# iMX6q_DDR3.net
KiCad netlist of a schematic drawn in Altium Designer
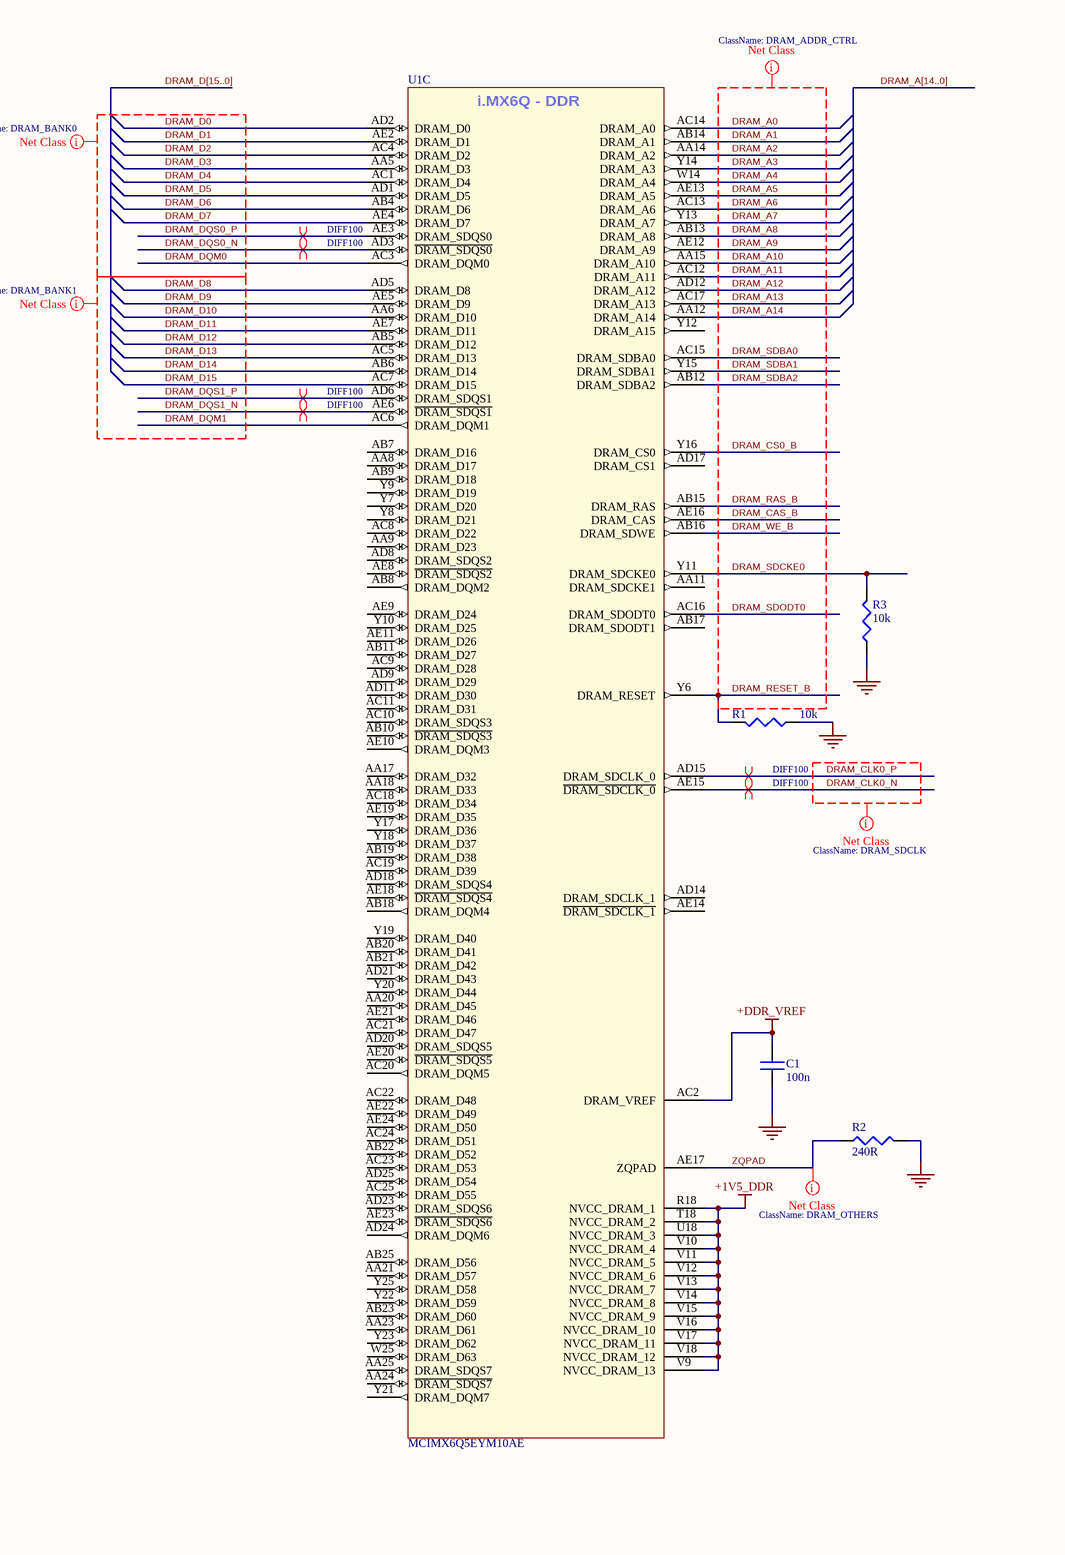
[diagram p0: iMX6q_DDR3.SchDoc, left]
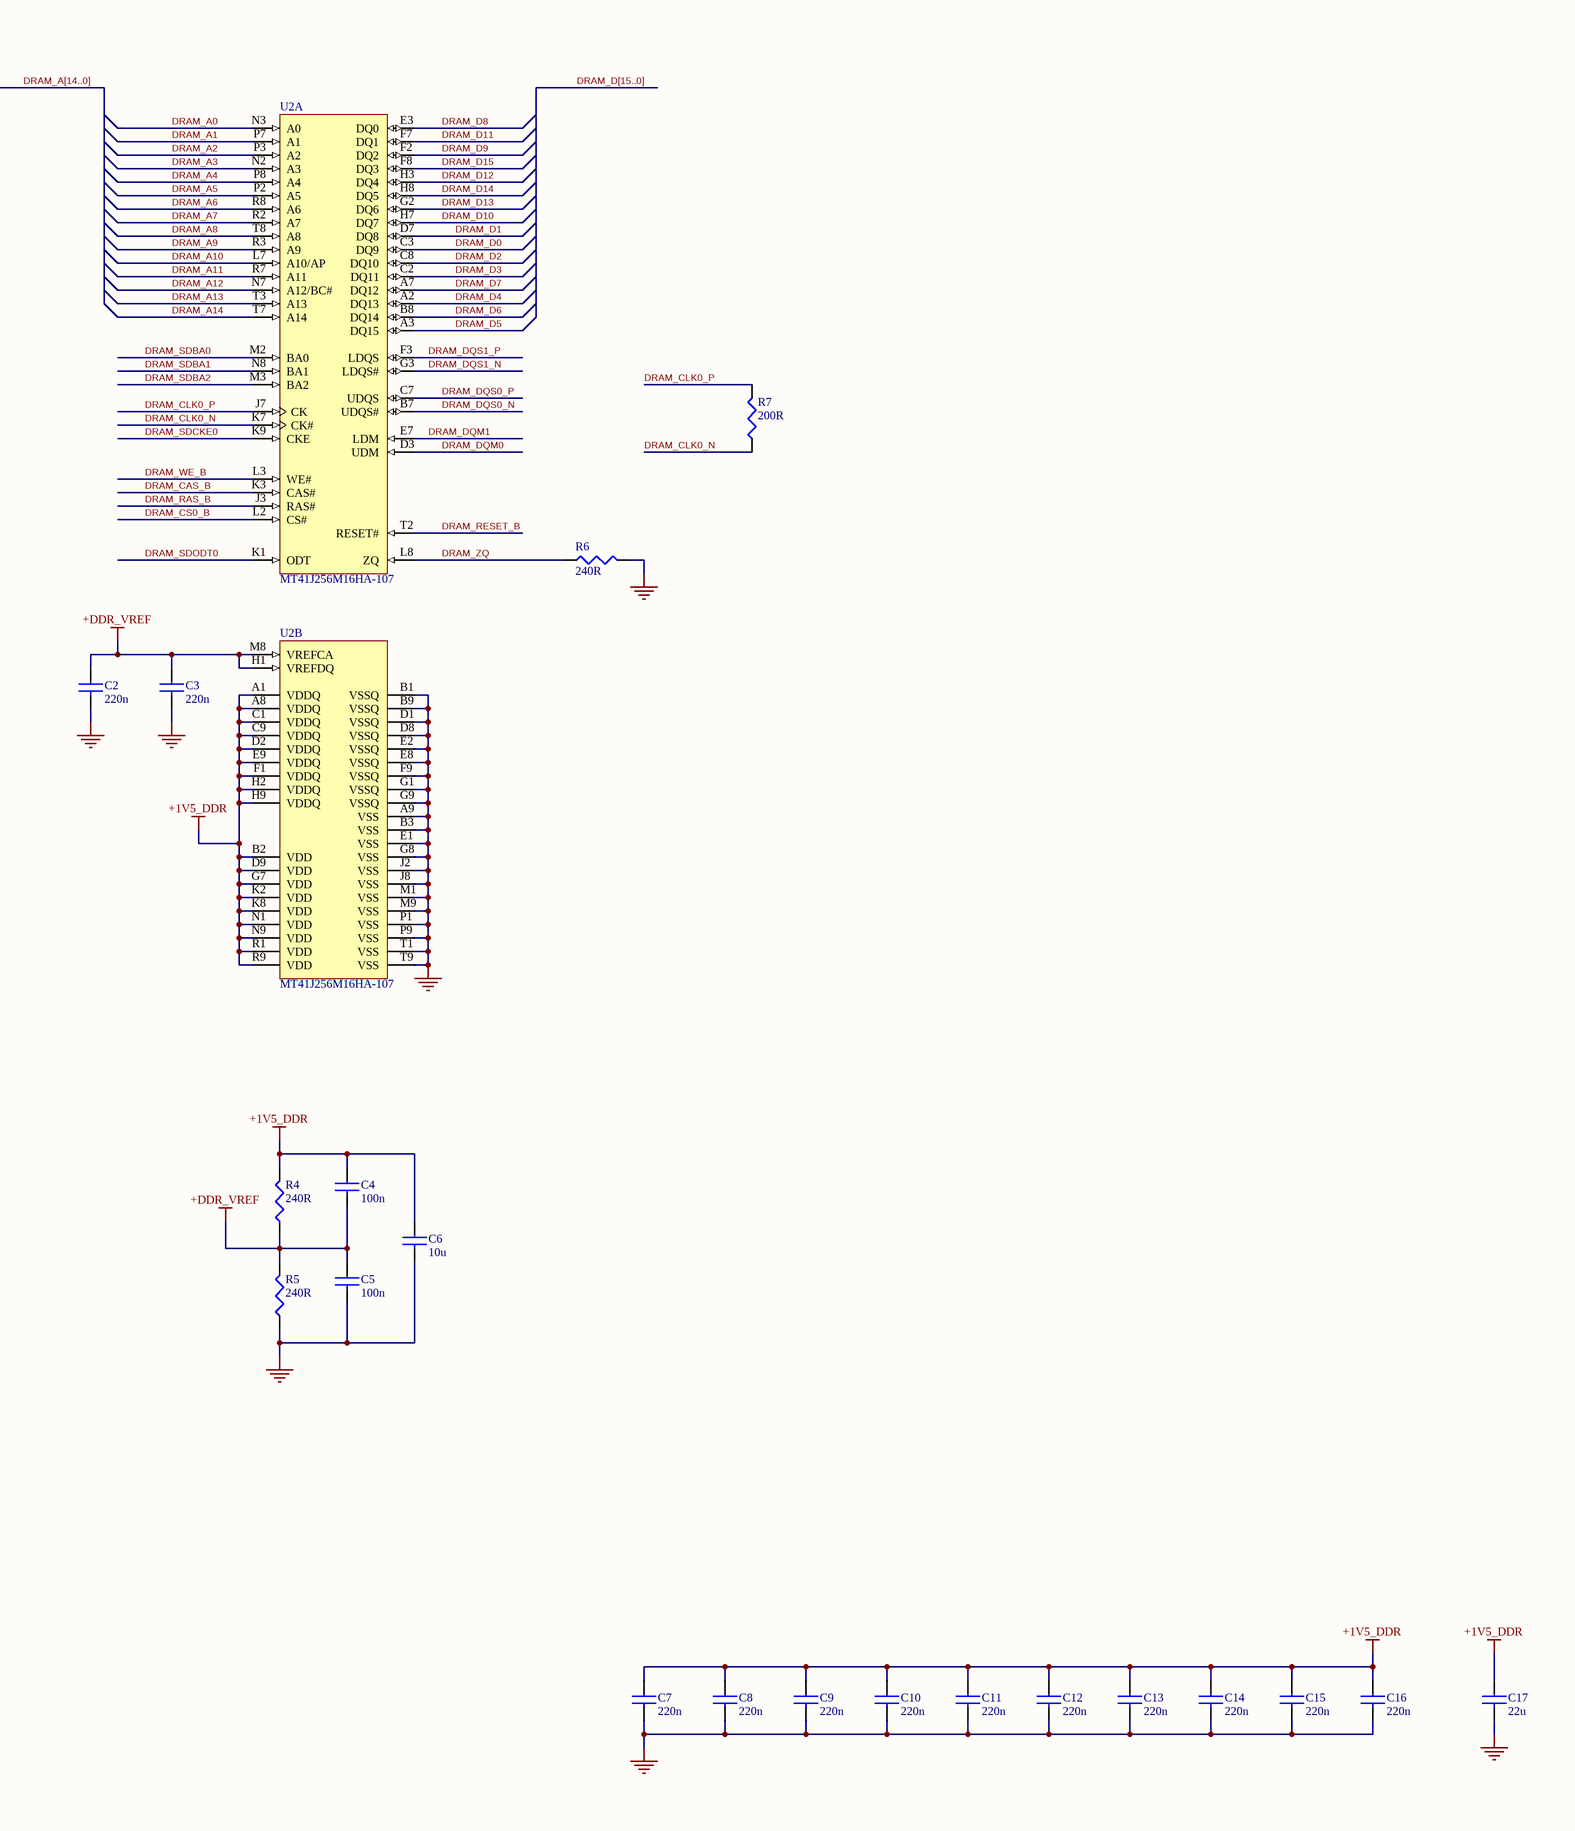
[diagram p1: iMX6q_DDR3.SchDoc, right]

(export (version "E")
  (design (tool "Eeschema 10.0.6"))
  (components
    (comp (ref "C1")
      (value "100n")
      (footprint "C0402")
      (description "CAP CER .10UF 50V X5R 10% 0402")
      (fields
        (field (name "MANUFACTURER") "TDK Corporation")
        (field (name "MANUFACTURER PART NUMBER") "C1005X5R1H104K")
      )
      (libsource (lib "iMX6 Rex_V1I1") (part "C1005X5R1H104K"))
    )
    (comp (ref "C2")
      (value "220n")
      (footprint "C0402")
      (description "CAP CER .22UF 25V X5R 20% 0402")
      (fields
        (field (name "MANUFACTURER") "TDK Corporation")
        (field (name "MANUFACTURER PART NUMBER") "C1005X5R1E224M")
      )
      (libsource (lib "iMX6 Rex_V1I1") (part "C1005X5R1E224M"))
    )
    (comp (ref "C3")
      (value "220n")
      (footprint "C0402")
      (description "CAP CER .22UF 25V X5R 20% 0402")
      (fields
        (field (name "MANUFACTURER") "TDK Corporation")
        (field (name "MANUFACTURER PART NUMBER") "C1005X5R1E224M")
      )
      (libsource (lib "iMX6 Rex_V1I1") (part "C1005X5R1E224M"))
    )
    (comp (ref "C4")
      (value "100n")
      (footprint "C0402")
      (description "CAP CER .10UF 50V X5R 10% 0402")
      (fields
        (field (name "MANUFACTURER") "TDK Corporation")
        (field (name "MANUFACTURER PART NUMBER") "C1005X5R1H104K")
      )
      (libsource (lib "iMX6 Rex_V1I1") (part "C1005X5R1H104K"))
    )
    (comp (ref "C5")
      (value "100n")
      (footprint "C0402")
      (description "CAP CER .10UF 50V X5R 10% 0402")
      (fields
        (field (name "MANUFACTURER") "TDK Corporation")
        (field (name "MANUFACTURER PART NUMBER") "C1005X5R1H104K")
      )
      (libsource (lib "iMX6 Rex_V1I1") (part "C1005X5R1H104K"))
    )
    (comp (ref "C6")
      (value "10u")
      (footprint "C0603")
      (description "CAP CER 10UF 6.3V X5R 20% 0603")
      (fields
        (field (name "MANUFACTURER") "TDK Corporation")
        (field (name "MANUFACTURER PART NUMBER") "C1608X5R0J106M")
      )
      (libsource (lib "iMX6 Rex_V1I1") (part "C1608X5R0J106M"))
    )
    (comp (ref "C7")
      (value "220n")
      (footprint "C0402")
      (description "CAP CER .22UF 25V X5R 20% 0402")
      (fields
        (field (name "MANUFACTURER") "TDK Corporation")
        (field (name "MANUFACTURER PART NUMBER") "C1005X5R1E224M")
      )
      (libsource (lib "iMX6 Rex_V1I1") (part "C1005X5R1E224M"))
    )
    (comp (ref "C8")
      (value "220n")
      (footprint "C0402")
      (description "CAP CER .22UF 25V X5R 20% 0402")
      (fields
        (field (name "MANUFACTURER") "TDK Corporation")
        (field (name "MANUFACTURER PART NUMBER") "C1005X5R1E224M")
      )
      (libsource (lib "iMX6 Rex_V1I1") (part "C1005X5R1E224M"))
    )
    (comp (ref "C9")
      (value "220n")
      (footprint "C0402")
      (description "CAP CER .22UF 25V X5R 20% 0402")
      (fields
        (field (name "MANUFACTURER") "TDK Corporation")
        (field (name "MANUFACTURER PART NUMBER") "C1005X5R1E224M")
      )
      (libsource (lib "iMX6 Rex_V1I1") (part "C1005X5R1E224M"))
    )
    (comp (ref "C10")
      (value "220n")
      (footprint "C0402")
      (description "CAP CER .22UF 25V X5R 20% 0402")
      (fields
        (field (name "MANUFACTURER") "TDK Corporation")
        (field (name "MANUFACTURER PART NUMBER") "C1005X5R1E224M")
      )
      (libsource (lib "iMX6 Rex_V1I1") (part "C1005X5R1E224M"))
    )
    (comp (ref "C11")
      (value "220n")
      (footprint "C0402")
      (description "CAP CER .22UF 25V X5R 20% 0402")
      (fields
        (field (name "MANUFACTURER") "TDK Corporation")
        (field (name "MANUFACTURER PART NUMBER") "C1005X5R1E224M")
      )
      (libsource (lib "iMX6 Rex_V1I1") (part "C1005X5R1E224M"))
    )
    (comp (ref "C12")
      (value "220n")
      (footprint "C0402")
      (description "CAP CER .22UF 25V X5R 20% 0402")
      (fields
        (field (name "MANUFACTURER") "TDK Corporation")
        (field (name "MANUFACTURER PART NUMBER") "C1005X5R1E224M")
      )
      (libsource (lib "iMX6 Rex_V1I1") (part "C1005X5R1E224M"))
    )
    (comp (ref "C13")
      (value "220n")
      (footprint "C0402")
      (description "CAP CER .22UF 25V X5R 20% 0402")
      (fields
        (field (name "MANUFACTURER") "TDK Corporation")
        (field (name "MANUFACTURER PART NUMBER") "C1005X5R1E224M")
      )
      (libsource (lib "iMX6 Rex_V1I1") (part "C1005X5R1E224M"))
    )
    (comp (ref "C14")
      (value "220n")
      (footprint "C0402")
      (description "CAP CER .22UF 25V X5R 20% 0402")
      (fields
        (field (name "MANUFACTURER") "TDK Corporation")
        (field (name "MANUFACTURER PART NUMBER") "C1005X5R1E224M")
      )
      (libsource (lib "iMX6 Rex_V1I1") (part "C1005X5R1E224M"))
    )
    (comp (ref "C15")
      (value "220n")
      (footprint "C0402")
      (description "CAP CER .22UF 25V X5R 20% 0402")
      (fields
        (field (name "MANUFACTURER") "TDK Corporation")
        (field (name "MANUFACTURER PART NUMBER") "C1005X5R1E224M")
      )
      (libsource (lib "iMX6 Rex_V1I1") (part "C1005X5R1E224M"))
    )
    (comp (ref "C16")
      (value "220n")
      (footprint "C0402")
      (description "CAP CER .22UF 25V X5R 20% 0402")
      (fields
        (field (name "MANUFACTURER") "TDK Corporation")
        (field (name "MANUFACTURER PART NUMBER") "C1005X5R1E224M")
      )
      (libsource (lib "iMX6 Rex_V1I1") (part "C1005X5R1E224M"))
    )
    (comp (ref "C17")
      (value "22u")
      (footprint "C0603")
      (description "CAP CER 22UF 4V 20% X5R 0603")
      (fields
        (field (name "MANUFACTURER") "Murata Electronics North America")
        (field (name "MANUFACTURER PART NUMBER") "GRM188R60G226MEA0L")
        (field (name ".CHECKED PCB") "RF, used by MM")
        (field (name ".CHECKED SCH") "MM, checked by RF")
        (field (name ".CREATOR") "MM")
      )
      (libsource (lib "iMX6 Rex_V1I1") (part "GRM188R60G226MEA0L"))
    )
    (comp (ref "R1")
      (value "10k")
      (footprint "R0402")
      (description "RES 10.0K OHM 1/16W 1% 0402 SMD")
      (fields
        (field (name "MANUFACTURER") "Yageo")
        (field (name "MANUFACTURER PART NUMBER") "RC0402FR-0710KL")
      )
      (libsource (lib "iMX6 Rex_V1I1") (part "RC0402FR-0710KL"))
    )
    (comp (ref "R2")
      (value "240R")
      (footprint "R0402")
      (description "RES TF 240 OHM 1% 0.0625W 0402")
      (fields
        (field (name "MANUFACTURER") "Stackpole Electronics Inc")
        (field (name "MANUFACTURER PART NUMBER") "RMCF0402FT240R")
      )
      (libsource (lib "iMX6 Rex_V1I1") (part "RMCF0402FT240R"))
    )
    (comp (ref "R3")
      (value "10k")
      (footprint "R0402")
      (description "RES 10.0K OHM 1/16W 1% 0402 SMD")
      (fields
        (field (name "MANUFACTURER") "Yageo")
        (field (name "MANUFACTURER PART NUMBER") "RC0402FR-0710KL")
      )
      (libsource (lib "iMX6 Rex_V1I1") (part "RC0402FR-0710KL"))
    )
    (comp (ref "R4")
      (value "240R")
      (footprint "R0402")
      (description "RES TF 240 OHM 1% 0.0625W 0402")
      (fields
        (field (name "MANUFACTURER") "Stackpole Electronics Inc")
        (field (name "MANUFACTURER PART NUMBER") "RMCF0402FT240R")
      )
      (libsource (lib "iMX6 Rex_V1I1") (part "RMCF0402FT240R"))
    )
    (comp (ref "R5")
      (value "240R")
      (footprint "R0402")
      (description "RES TF 240 OHM 1% 0.0625W 0402")
      (fields
        (field (name "MANUFACTURER") "Stackpole Electronics Inc")
        (field (name "MANUFACTURER PART NUMBER") "RMCF0402FT240R")
      )
      (libsource (lib "iMX6 Rex_V1I1") (part "RMCF0402FT240R"))
    )
    (comp (ref "R6")
      (value "240R")
      (footprint "R0402")
      (description "RES TF 240 OHM 1% 0.0625W 0402")
      (fields
        (field (name "MANUFACTURER") "Stackpole Electronics Inc")
        (field (name "MANUFACTURER PART NUMBER") "RMCF0402FT240R")
      )
      (libsource (lib "iMX6 Rex_V1I1") (part "RMCF0402FT240R"))
    )
    (comp (ref "R7")
      (value "200R")
      (footprint "R0402")
      (description "RES 200 OHM 1/16W 1% 0402 SMD")
      (fields
        (field (name "MANUFACTURER") "Vishay Dale")
        (field (name "MANUFACTURER PART NUMBER") "CRCW0402200RFKED")
        (field (name ".CHECKED PCB") "RF, used by MM")
        (field (name ".CHECKED SCH") "MM, checked by RF")
        (field (name ".CREATOR") "MM")
      )
      (libsource (lib "iMX6 Rex_V1I1") (part "CRCW0402200RFKED"))
    )
    (comp (ref "U1")
      (value "MCIMX6Q5EYM10AE")
      (footprint "PBGA624")
      (description "IC MCU 32BIT ARM QUAD 624FCBGA")
      (fields
        (field (name "MANUFACTURER") "Freescale Semiconductor")
        (field (name ".CREATOR") "MM")
        (field (name ".CHECKED PCB") "MM, checked by RF")
        (field (name ".CHECKED SCH") "MM")
      )
      (libsource (lib "iMX6 Rex_V1I1") (part "MCIMX6Q5EYM10AC"))
    )
    (comp (ref "U2")
      (value "MT41J256M16HA-107")
      (footprint "MICT-HA-96")
      (description "4Gb DDR3-1866 SDRAM, 256Mb x 16, 1.071ns, 1.5V, 0 to 95 degC, 96-Ball FBGA, Pb-Free")
      (fields (field (name "VOLTAGE") "1.5V ") (field (name "MANUFACTURER") "Micron"))
      (libsource (lib "Micron Memory DDR3 SDRAM") (part "MT41J256M16HA-107"))
    )
  )
  (nets
    (net (code "1") (name "+1V5_DDR") (class "Default")
      (node (ref "C10") (pin "1") (pinfunction "1_1") (pintype "passive"))
      (node (ref "C11") (pin "1") (pinfunction "1_1") (pintype "passive"))
      (node (ref "C12") (pin "1") (pinfunction "1_1") (pintype "passive"))
      (node (ref "C13") (pin "1") (pinfunction "1_1") (pintype "passive"))
      (node (ref "C14") (pin "1") (pinfunction "1_1") (pintype "passive"))
      (node (ref "C15") (pin "1") (pinfunction "1_1") (pintype "passive"))
      (node (ref "C16") (pin "1") (pinfunction "1_1") (pintype "passive"))
      (node (ref "C17") (pin "1") (pinfunction "1_1") (pintype "passive"))
      (node (ref "C4") (pin "1") (pinfunction "1_1") (pintype "passive"))
      (node (ref "C6") (pin "1") (pinfunction "1_1") (pintype "passive"))
      (node (ref "C7") (pin "1") (pinfunction "1_1") (pintype "passive"))
      (node (ref "C8") (pin "1") (pinfunction "1_1") (pintype "passive"))
      (node (ref "C9") (pin "1") (pinfunction "1_1") (pintype "passive"))
      (node (ref "R4") (pin "2") (pinfunction "2_2") (pintype "passive"))
      (node (ref "U1") (pin "R18") (pinfunction "NVCC_DRAM_1_R18") (pintype "power_in"))
      (node (ref "U1") (pin "T18") (pinfunction "NVCC_DRAM_2_T18") (pintype "power_in"))
      (node (ref "U1") (pin "U18") (pinfunction "NVCC_DRAM_3_U18") (pintype "power_in"))
      (node (ref "U1") (pin "V10") (pinfunction "NVCC_DRAM_4_V10") (pintype "power_in"))
      (node (ref "U1") (pin "V11") (pinfunction "NVCC_DRAM_5_V11") (pintype "power_in"))
      (node (ref "U1") (pin "V12") (pinfunction "NVCC_DRAM_6_V12") (pintype "power_in"))
      (node (ref "U1") (pin "V13") (pinfunction "NVCC_DRAM_7_V13") (pintype "power_in"))
      (node (ref "U1") (pin "V14") (pinfunction "NVCC_DRAM_8_V14") (pintype "power_in"))
      (node (ref "U1") (pin "V15") (pinfunction "NVCC_DRAM_9_V15") (pintype "power_in"))
      (node (ref "U1") (pin "V16") (pinfunction "NVCC_DRAM_10_V16") (pintype "power_in"))
      (node (ref "U1") (pin "V17") (pinfunction "NVCC_DRAM_11_V17") (pintype "power_in"))
      (node (ref "U1") (pin "V18") (pinfunction "NVCC_DRAM_12_V18") (pintype "power_in"))
      (node (ref "U1") (pin "V9") (pinfunction "NVCC_DRAM_13_V9") (pintype "power_in"))
      (node (ref "U2") (pin "A1") (pinfunction "VDDQ_A1") (pintype "power_in"))
      (node (ref "U2") (pin "A8") (pinfunction "VDDQ_A8") (pintype "power_in"))
      (node (ref "U2") (pin "B2") (pinfunction "VDD_B2") (pintype "power_in"))
      (node (ref "U2") (pin "C1") (pinfunction "VDDQ_C1") (pintype "power_in"))
      (node (ref "U2") (pin "C9") (pinfunction "VDDQ_C9") (pintype "power_in"))
      (node (ref "U2") (pin "D2") (pinfunction "VDDQ_D2") (pintype "power_in"))
      (node (ref "U2") (pin "D9") (pinfunction "VDD_D9") (pintype "power_in"))
      (node (ref "U2") (pin "E9") (pinfunction "VDDQ_E9") (pintype "power_in"))
      (node (ref "U2") (pin "F1") (pinfunction "VDDQ_F1") (pintype "power_in"))
      (node (ref "U2") (pin "G7") (pinfunction "VDD_G7") (pintype "power_in"))
      (node (ref "U2") (pin "H2") (pinfunction "VDDQ_H2") (pintype "power_in"))
      (node (ref "U2") (pin "H9") (pinfunction "VDDQ_H9") (pintype "power_in"))
      (node (ref "U2") (pin "K2") (pinfunction "VDD_K2") (pintype "power_in"))
      (node (ref "U2") (pin "K8") (pinfunction "VDD_K8") (pintype "power_in"))
      (node (ref "U2") (pin "N1") (pinfunction "VDD_N1") (pintype "power_in"))
      (node (ref "U2") (pin "N9") (pinfunction "VDD_N9") (pintype "power_in"))
      (node (ref "U2") (pin "R1") (pinfunction "VDD_R1") (pintype "power_in"))
      (node (ref "U2") (pin "R9") (pinfunction "VDD_R9") (pintype "power_in"))
    )
    (net (code "2") (name "+DDR_VREF") (class "Default")
      (node (ref "C1") (pin "1") (pinfunction "1_1") (pintype "passive"))
      (node (ref "C2") (pin "1") (pinfunction "1_1") (pintype "passive"))
      (node (ref "C3") (pin "1") (pinfunction "1_1") (pintype "passive"))
      (node (ref "C4") (pin "2") (pinfunction "2_2") (pintype "passive"))
      (node (ref "C5") (pin "1") (pinfunction "1_1") (pintype "passive"))
      (node (ref "R4") (pin "1") (pinfunction "1_1") (pintype "passive"))
      (node (ref "R5") (pin "2") (pinfunction "2_2") (pintype "passive"))
      (node (ref "U1") (pin "AC2") (pinfunction "DRAM_VREF_AC2") (pintype "power_in"))
      (node (ref "U2") (pin "H1") (pinfunction "VREFDQ_H1") (pintype "input"))
      (node (ref "U2") (pin "M8") (pinfunction "VREFCA_M8") (pintype "input"))
    )
    (net (code "3") (name "/DRAM_A0") (class "Default")
      (node (ref "U1") (pin "AC14") (pinfunction "DRAM_A0_AC14") (pintype "output"))
      (node (ref "U2") (pin "N3") (pinfunction "A0_N3") (pintype "input"))
    )
    (net (code "4") (name "/DRAM_A1") (class "Default")
      (node (ref "U1") (pin "AB14") (pinfunction "DRAM_A1_AB14") (pintype "output"))
      (node (ref "U2") (pin "P7") (pinfunction "A1_P7") (pintype "input"))
    )
    (net (code "5") (name "/DRAM_A2") (class "Default")
      (node (ref "U1") (pin "AA14") (pinfunction "DRAM_A2_AA14") (pintype "output"))
      (node (ref "U2") (pin "P3") (pinfunction "A2_P3") (pintype "input"))
    )
    (net (code "6") (name "/DRAM_A3") (class "Default")
      (node (ref "U1") (pin "Y14") (pinfunction "DRAM_A3_Y14") (pintype "output"))
      (node (ref "U2") (pin "N2") (pinfunction "A3_N2") (pintype "input"))
    )
    (net (code "7") (name "/DRAM_A4") (class "Default")
      (node (ref "U1") (pin "W14") (pinfunction "DRAM_A4_W14") (pintype "output"))
      (node (ref "U2") (pin "P8") (pinfunction "A4_P8") (pintype "input"))
    )
    (net (code "8") (name "/DRAM_A5") (class "Default")
      (node (ref "U1") (pin "AE13") (pinfunction "DRAM_A5_AE13") (pintype "output"))
      (node (ref "U2") (pin "P2") (pinfunction "A5_P2") (pintype "input"))
    )
    (net (code "9") (name "/DRAM_A6") (class "Default")
      (node (ref "U1") (pin "AC13") (pinfunction "DRAM_A6_AC13") (pintype "output"))
      (node (ref "U2") (pin "R8") (pinfunction "A6_R8") (pintype "input"))
    )
    (net (code "10") (name "/DRAM_A7") (class "Default")
      (node (ref "U1") (pin "Y13") (pinfunction "DRAM_A7_Y13") (pintype "output"))
      (node (ref "U2") (pin "R2") (pinfunction "A7_R2") (pintype "input"))
    )
    (net (code "11") (name "/DRAM_A8") (class "Default")
      (node (ref "U1") (pin "AB13") (pinfunction "DRAM_A8_AB13") (pintype "output"))
      (node (ref "U2") (pin "T8") (pinfunction "A8_T8") (pintype "input"))
    )
    (net (code "12") (name "/DRAM_A9") (class "Default")
      (node (ref "U1") (pin "AE12") (pinfunction "DRAM_A9_AE12") (pintype "output"))
      (node (ref "U2") (pin "R3") (pinfunction "A9_R3") (pintype "input"))
    )
    (net (code "13") (name "/DRAM_A10") (class "Default")
      (node (ref "U1") (pin "AA15") (pinfunction "DRAM_A10_AA15") (pintype "output"))
      (node (ref "U2") (pin "L7") (pinfunction "A10/AP_L7") (pintype "input"))
    )
    (net (code "14") (name "/DRAM_A11") (class "Default")
      (node (ref "U1") (pin "AC12") (pinfunction "DRAM_A11_AC12") (pintype "output"))
      (node (ref "U2") (pin "R7") (pinfunction "A11_R7") (pintype "input"))
    )
    (net (code "15") (name "/DRAM_A12") (class "Default")
      (node (ref "U1") (pin "AD12") (pinfunction "DRAM_A12_AD12") (pintype "output"))
      (node (ref "U2") (pin "N7") (pinfunction "A12/BC#_N7") (pintype "input"))
    )
    (net (code "16") (name "/DRAM_A13") (class "Default")
      (node (ref "U1") (pin "AC17") (pinfunction "DRAM_A13_AC17") (pintype "output"))
      (node (ref "U2") (pin "T3") (pinfunction "A13_T3") (pintype "input"))
    )
    (net (code "17") (name "/DRAM_A14") (class "Default")
      (node (ref "U1") (pin "AA12") (pinfunction "DRAM_A14_AA12") (pintype "output"))
      (node (ref "U2") (pin "T7") (pinfunction "A14_T7") (pintype "input"))
    )
    (net (code "19") (name "/DRAM_CAS_B") (class "Default")
      (node (ref "U1") (pin "AE16") (pinfunction "DRAM_CAS_AE16") (pintype "output"))
      (node (ref "U2") (pin "K3") (pinfunction "CAS#_K3") (pintype "input"))
    )
    (net (code "20") (name "/DRAM_CLK0_N") (class "Default")
      (node (ref "R7") (pin "1") (pinfunction "1_1") (pintype "passive"))
      (node (ref "U1") (pin "AE15") (pinfunction "~{DRAM_SDCLK_0}_AE15") (pintype "output"))
      (node (ref "U2") (pin "K7") (pinfunction "CK#_K7") (pintype "input"))
    )
    (net (code "21") (name "/DRAM_CLK0_P") (class "Default")
      (node (ref "R7") (pin "2") (pinfunction "2_2") (pintype "passive"))
      (node (ref "U1") (pin "AD15") (pinfunction "DRAM_SDCLK_0_AD15") (pintype "output"))
      (node (ref "U2") (pin "J7") (pinfunction "CK_J7") (pintype "input"))
    )
    (net (code "22") (name "/DRAM_CS0_B") (class "Default")
      (node (ref "U1") (pin "Y16") (pinfunction "DRAM_CS0_Y16") (pintype "output"))
      (node (ref "U2") (pin "L2") (pinfunction "CS#_L2") (pintype "input"))
    )
    (net (code "23") (name "/DRAM_D0") (class "Default")
      (node (ref "U1") (pin "AD2") (pinfunction "DRAM_D0_AD2") (pintype "bidirectional"))
      (node (ref "U2") (pin "C3") (pinfunction "DQ9_C3") (pintype "bidirectional"))
    )
    (net (code "24") (name "/DRAM_D1") (class "Default")
      (node (ref "U1") (pin "AE2") (pinfunction "DRAM_D1_AE2") (pintype "bidirectional"))
      (node (ref "U2") (pin "D7") (pinfunction "DQ8_D7") (pintype "bidirectional"))
    )
    (net (code "25") (name "/DRAM_D2") (class "Default")
      (node (ref "U1") (pin "AC4") (pinfunction "DRAM_D2_AC4") (pintype "bidirectional"))
      (node (ref "U2") (pin "C8") (pinfunction "DQ10_C8") (pintype "bidirectional"))
    )
    (net (code "26") (name "/DRAM_D3") (class "Default")
      (node (ref "U1") (pin "AA5") (pinfunction "DRAM_D3_AA5") (pintype "bidirectional"))
      (node (ref "U2") (pin "C2") (pinfunction "DQ11_C2") (pintype "bidirectional"))
    )
    (net (code "27") (name "/DRAM_D4") (class "Default")
      (node (ref "U1") (pin "AC1") (pinfunction "DRAM_D4_AC1") (pintype "bidirectional"))
      (node (ref "U2") (pin "A2") (pinfunction "DQ13_A2") (pintype "bidirectional"))
    )
    (net (code "28") (name "/DRAM_D5") (class "Default")
      (node (ref "U1") (pin "AD1") (pinfunction "DRAM_D5_AD1") (pintype "bidirectional"))
      (node (ref "U2") (pin "A3") (pinfunction "DQ15_A3") (pintype "bidirectional"))
    )
    (net (code "29") (name "/DRAM_D6") (class "Default")
      (node (ref "U1") (pin "AB4") (pinfunction "DRAM_D6_AB4") (pintype "bidirectional"))
      (node (ref "U2") (pin "B8") (pinfunction "DQ14_B8") (pintype "bidirectional"))
    )
    (net (code "30") (name "/DRAM_D7") (class "Default")
      (node (ref "U1") (pin "AE4") (pinfunction "DRAM_D7_AE4") (pintype "bidirectional"))
      (node (ref "U2") (pin "A7") (pinfunction "DQ12_A7") (pintype "bidirectional"))
    )
    (net (code "31") (name "/DRAM_D8") (class "Default")
      (node (ref "U1") (pin "AD5") (pinfunction "DRAM_D8_AD5") (pintype "bidirectional"))
      (node (ref "U2") (pin "E3") (pinfunction "DQ0_E3") (pintype "bidirectional"))
    )
    (net (code "32") (name "/DRAM_D9") (class "Default")
      (node (ref "U1") (pin "AE5") (pinfunction "DRAM_D9_AE5") (pintype "bidirectional"))
      (node (ref "U2") (pin "F2") (pinfunction "DQ2_F2") (pintype "bidirectional"))
    )
    (net (code "33") (name "/DRAM_D10") (class "Default")
      (node (ref "U1") (pin "AA6") (pinfunction "DRAM_D10_AA6") (pintype "bidirectional"))
      (node (ref "U2") (pin "H7") (pinfunction "DQ7_H7") (pintype "bidirectional"))
    )
    (net (code "34") (name "/DRAM_D11") (class "Default")
      (node (ref "U1") (pin "AE7") (pinfunction "DRAM_D11_AE7") (pintype "bidirectional"))
      (node (ref "U2") (pin "F7") (pinfunction "DQ1_F7") (pintype "bidirectional"))
    )
    (net (code "35") (name "/DRAM_D12") (class "Default")
      (node (ref "U1") (pin "AB5") (pinfunction "DRAM_D12_AB5") (pintype "bidirectional"))
      (node (ref "U2") (pin "H3") (pinfunction "DQ4_H3") (pintype "bidirectional"))
    )
    (net (code "36") (name "/DRAM_D13") (class "Default")
      (node (ref "U1") (pin "AC5") (pinfunction "DRAM_D13_AC5") (pintype "bidirectional"))
      (node (ref "U2") (pin "G2") (pinfunction "DQ6_G2") (pintype "bidirectional"))
    )
    (net (code "37") (name "/DRAM_D14") (class "Default")
      (node (ref "U1") (pin "AB6") (pinfunction "DRAM_D14_AB6") (pintype "bidirectional"))
      (node (ref "U2") (pin "H8") (pinfunction "DQ5_H8") (pintype "bidirectional"))
    )
    (net (code "38") (name "/DRAM_D15") (class "Default")
      (node (ref "U1") (pin "AC7") (pinfunction "DRAM_D15_AC7") (pintype "bidirectional"))
      (node (ref "U2") (pin "F8") (pinfunction "DQ3_F8") (pintype "bidirectional"))
    )
    (net (code "39") (name "/DRAM_DQM0") (class "Default")
      (node (ref "U1") (pin "AC3") (pinfunction "DRAM_DQM0_AC3") (pintype "output"))
      (node (ref "U2") (pin "D3") (pinfunction "UDM_D3") (pintype "input"))
    )
    (net (code "40") (name "/DRAM_DQM1") (class "Default")
      (node (ref "U1") (pin "AC6") (pinfunction "DRAM_DQM1_AC6") (pintype "output"))
      (node (ref "U2") (pin "E7") (pinfunction "LDM_E7") (pintype "input"))
    )
    (net (code "41") (name "/DRAM_DQS0_N") (class "Default")
      (node (ref "U1") (pin "AD3") (pinfunction "~{DRAM_SDQS0}_AD3") (pintype "bidirectional"))
      (node (ref "U2") (pin "B7") (pinfunction "UDQS#_B7") (pintype "bidirectional"))
    )
    (net (code "42") (name "/DRAM_DQS0_P") (class "Default")
      (node (ref "U1") (pin "AE3") (pinfunction "DRAM_SDQS0_AE3") (pintype "bidirectional"))
      (node (ref "U2") (pin "C7") (pinfunction "UDQS_C7") (pintype "bidirectional"))
    )
    (net (code "43") (name "/DRAM_DQS1_N") (class "Default")
      (node (ref "U1") (pin "AE6") (pinfunction "~{DRAM_SDQS1}_AE6") (pintype "bidirectional"))
      (node (ref "U2") (pin "G3") (pinfunction "LDQS#_G3") (pintype "bidirectional"))
    )
    (net (code "44") (name "/DRAM_DQS1_P") (class "Default")
      (node (ref "U1") (pin "AD6") (pinfunction "DRAM_SDQS1_AD6") (pintype "bidirectional"))
      (node (ref "U2") (pin "F3") (pinfunction "LDQS_F3") (pintype "bidirectional"))
    )
    (net (code "46") (name "/DRAM_RAS_B") (class "Default")
      (node (ref "U1") (pin "AB15") (pinfunction "DRAM_RAS_AB15") (pintype "output"))
      (node (ref "U2") (pin "J3") (pinfunction "RAS#_J3") (pintype "input"))
    )
    (net (code "47") (name "/DRAM_RESET_B") (class "Default")
      (node (ref "R1") (pin "2") (pinfunction "2_2") (pintype "passive"))
      (node (ref "U1") (pin "Y6") (pinfunction "DRAM_RESET_Y6") (pintype "output"))
      (node (ref "U2") (pin "T2") (pinfunction "RESET#_T2") (pintype "input"))
    )
    (net (code "48") (name "/DRAM_SDBA0") (class "Default")
      (node (ref "U1") (pin "AC15") (pinfunction "DRAM_SDBA0_AC15") (pintype "output"))
      (node (ref "U2") (pin "M2") (pinfunction "BA0_M2") (pintype "input"))
    )
    (net (code "49") (name "/DRAM_SDBA1") (class "Default")
      (node (ref "U1") (pin "Y15") (pinfunction "DRAM_SDBA1_Y15") (pintype "output"))
      (node (ref "U2") (pin "N8") (pinfunction "BA1_N8") (pintype "input"))
    )
    (net (code "50") (name "/DRAM_SDBA2") (class "Default")
      (node (ref "U1") (pin "AB12") (pinfunction "DRAM_SDBA2_AB12") (pintype "output"))
      (node (ref "U2") (pin "M3") (pinfunction "BA2_M3") (pintype "input"))
    )
    (net (code "51") (name "/DRAM_SDCKE0") (class "Default")
      (node (ref "R3") (pin "2") (pinfunction "2_2") (pintype "passive"))
      (node (ref "U1") (pin "Y11") (pinfunction "DRAM_SDCKE0_Y11") (pintype "output"))
      (node (ref "U2") (pin "K9") (pinfunction "CKE_K9") (pintype "input"))
    )
    (net (code "52") (name "/DRAM_SDODT0") (class "Default")
      (node (ref "U1") (pin "AC16") (pinfunction "DRAM_SDODT0_AC16") (pintype "output"))
      (node (ref "U2") (pin "K1") (pinfunction "ODT_K1") (pintype "input"))
    )
    (net (code "53") (name "/DRAM_WE_B") (class "Default")
      (node (ref "U1") (pin "AB16") (pinfunction "DRAM_SDWE_AB16") (pintype "output"))
      (node (ref "U2") (pin "L3") (pinfunction "WE#_L3") (pintype "input"))
    )
    (net (code "54") (name "/DRAM_ZQ") (class "Default")
      (node (ref "R6") (pin "2") (pinfunction "2_2") (pintype "passive"))
      (node (ref "U2") (pin "L8") (pinfunction "ZQ_L8") (pintype "input"))
    )
    (net (code "55") (name "/ZQPAD") (class "Default")
      (node (ref "R2") (pin "1") (pinfunction "1_1") (pintype "passive"))
      (node (ref "U1") (pin "AE17") (pinfunction "ZQPAD_AE17") (pintype "passive"))
    )
    (net (code "56") (name "GND") (class "Default")
      (node (ref "C1") (pin "2") (pinfunction "2_2") (pintype "passive"))
      (node (ref "C10") (pin "2") (pinfunction "2_2") (pintype "passive"))
      (node (ref "C11") (pin "2") (pinfunction "2_2") (pintype "passive"))
      (node (ref "C12") (pin "2") (pinfunction "2_2") (pintype "passive"))
      (node (ref "C13") (pin "2") (pinfunction "2_2") (pintype "passive"))
      (node (ref "C14") (pin "2") (pinfunction "2_2") (pintype "passive"))
      (node (ref "C15") (pin "2") (pinfunction "2_2") (pintype "passive"))
      (node (ref "C16") (pin "2") (pinfunction "2_2") (pintype "passive"))
      (node (ref "C17") (pin "2") (pinfunction "2_2") (pintype "passive"))
      (node (ref "C2") (pin "2") (pinfunction "2_2") (pintype "passive"))
      (node (ref "C3") (pin "2") (pinfunction "2_2") (pintype "passive"))
      (node (ref "C5") (pin "2") (pinfunction "2_2") (pintype "passive"))
      (node (ref "C6") (pin "2") (pinfunction "2_2") (pintype "passive"))
      (node (ref "C7") (pin "2") (pinfunction "2_2") (pintype "passive"))
      (node (ref "C8") (pin "2") (pinfunction "2_2") (pintype "passive"))
      (node (ref "C9") (pin "2") (pinfunction "2_2") (pintype "passive"))
      (node (ref "R1") (pin "1") (pinfunction "1_1") (pintype "passive"))
      (node (ref "R2") (pin "2") (pinfunction "2_2") (pintype "passive"))
      (node (ref "R3") (pin "1") (pinfunction "1_1") (pintype "passive"))
      (node (ref "R5") (pin "1") (pinfunction "1_1") (pintype "passive"))
      (node (ref "R6") (pin "1") (pinfunction "1_1") (pintype "passive"))
      (node (ref "U2") (pin "A9") (pinfunction "VSS_A9") (pintype "power_in"))
      (node (ref "U2") (pin "B1") (pinfunction "VSSQ_B1") (pintype "power_in"))
      (node (ref "U2") (pin "B3") (pinfunction "VSS_B3") (pintype "power_in"))
      (node (ref "U2") (pin "B9") (pinfunction "VSSQ_B9") (pintype "power_in"))
      (node (ref "U2") (pin "D1") (pinfunction "VSSQ_D1") (pintype "power_in"))
      (node (ref "U2") (pin "D8") (pinfunction "VSSQ_D8") (pintype "power_in"))
      (node (ref "U2") (pin "E1") (pinfunction "VSS_E1") (pintype "power_in"))
      (node (ref "U2") (pin "E2") (pinfunction "VSSQ_E2") (pintype "power_in"))
      (node (ref "U2") (pin "E8") (pinfunction "VSSQ_E8") (pintype "power_in"))
      (node (ref "U2") (pin "F9") (pinfunction "VSSQ_F9") (pintype "power_in"))
      (node (ref "U2") (pin "G1") (pinfunction "VSSQ_G1") (pintype "power_in"))
      (node (ref "U2") (pin "G8") (pinfunction "VSS_G8") (pintype "power_in"))
      (node (ref "U2") (pin "G9") (pinfunction "VSSQ_G9") (pintype "power_in"))
      (node (ref "U2") (pin "J2") (pinfunction "VSS_J2") (pintype "power_in"))
      (node (ref "U2") (pin "J8") (pinfunction "VSS_J8") (pintype "power_in"))
      (node (ref "U2") (pin "M1") (pinfunction "VSS_M1") (pintype "power_in"))
      (node (ref "U2") (pin "M9") (pinfunction "VSS_M9") (pintype "power_in"))
      (node (ref "U2") (pin "P1") (pinfunction "VSS_P1") (pintype "power_in"))
      (node (ref "U2") (pin "P9") (pinfunction "VSS_P9") (pintype "power_in"))
      (node (ref "U2") (pin "T1") (pinfunction "VSS_T1") (pintype "power_in"))
      (node (ref "U2") (pin "T9") (pinfunction "VSS_T9") (pintype "power_in"))
    )
    (net (code "57") (name "unconnected-(U1C-DRAM_A15-PadY12)") (class "Default")
      (node (ref "U1") (pin "Y12") (pinfunction "DRAM_A15_Y12") (pintype "output"))
    )
    (net (code "58") (name "unconnected-(U1C-DRAM_CS1-PadAD17)") (class "Default")
      (node (ref "U1") (pin "AD17") (pinfunction "DRAM_CS1_AD17") (pintype "output"))
    )
    (net (code "59") (name "unconnected-(U1C-DRAM_D16-PadAB7)") (class "Default")
      (node (ref "U1") (pin "AB7") (pinfunction "DRAM_D16_AB7") (pintype "bidirectional"))
    )
    (net (code "60") (name "unconnected-(U1C-DRAM_D17-PadAA8)") (class "Default")
      (node (ref "U1") (pin "AA8") (pinfunction "DRAM_D17_AA8") (pintype "bidirectional"))
    )
    (net (code "61") (name "unconnected-(U1C-DRAM_D18-PadAB9)") (class "Default")
      (node (ref "U1") (pin "AB9") (pinfunction "DRAM_D18_AB9") (pintype "bidirectional"))
    )
    (net (code "62") (name "unconnected-(U1C-DRAM_D19-PadY9)") (class "Default")
      (node (ref "U1") (pin "Y9") (pinfunction "DRAM_D19_Y9") (pintype "bidirectional"))
    )
    (net (code "63") (name "unconnected-(U1C-DRAM_D20-PadY7)") (class "Default")
      (node (ref "U1") (pin "Y7") (pinfunction "DRAM_D20_Y7") (pintype "bidirectional"))
    )
    (net (code "64") (name "unconnected-(U1C-DRAM_D21-PadY8)") (class "Default")
      (node (ref "U1") (pin "Y8") (pinfunction "DRAM_D21_Y8") (pintype "bidirectional"))
    )
    (net (code "65") (name "unconnected-(U1C-DRAM_D22-PadAC8)") (class "Default")
      (node (ref "U1") (pin "AC8") (pinfunction "DRAM_D22_AC8") (pintype "bidirectional"))
    )
    (net (code "66") (name "unconnected-(U1C-DRAM_D23-PadAA9)") (class "Default")
      (node (ref "U1") (pin "AA9") (pinfunction "DRAM_D23_AA9") (pintype "bidirectional"))
    )
    (net (code "67") (name "unconnected-(U1C-DRAM_D24-PadAE9)") (class "Default")
      (node (ref "U1") (pin "AE9") (pinfunction "DRAM_D24_AE9") (pintype "bidirectional"))
    )
    (net (code "68") (name "unconnected-(U1C-DRAM_D25-PadY10)") (class "Default")
      (node (ref "U1") (pin "Y10") (pinfunction "DRAM_D25_Y10") (pintype "bidirectional"))
    )
    (net (code "69") (name "unconnected-(U1C-DRAM_D26-PadAE11)") (class "Default")
      (node (ref "U1") (pin "AE11") (pinfunction "DRAM_D26_AE11") (pintype "bidirectional"))
    )
    (net (code "70") (name "unconnected-(U1C-DRAM_D27-PadAB11)") (class "Default")
      (node (ref "U1") (pin "AB11") (pinfunction "DRAM_D27_AB11") (pintype "bidirectional"))
    )
    (net (code "71") (name "unconnected-(U1C-DRAM_D28-PadAC9)") (class "Default")
      (node (ref "U1") (pin "AC9") (pinfunction "DRAM_D28_AC9") (pintype "bidirectional"))
    )
    (net (code "72") (name "unconnected-(U1C-DRAM_D29-PadAD9)") (class "Default")
      (node (ref "U1") (pin "AD9") (pinfunction "DRAM_D29_AD9") (pintype "bidirectional"))
    )
    (net (code "73") (name "unconnected-(U1C-DRAM_D30-PadAD11)") (class "Default")
      (node (ref "U1") (pin "AD11") (pinfunction "DRAM_D30_AD11") (pintype "bidirectional"))
    )
    (net (code "74") (name "unconnected-(U1C-DRAM_D31-PadAC11)") (class "Default")
      (node (ref "U1") (pin "AC11") (pinfunction "DRAM_D31_AC11") (pintype "bidirectional"))
    )
    (net (code "75") (name "unconnected-(U1C-DRAM_D32-PadAA17)") (class "Default")
      (node (ref "U1") (pin "AA17") (pinfunction "DRAM_D32_AA17") (pintype "bidirectional"))
    )
    (net (code "76") (name "unconnected-(U1C-DRAM_D33-PadAA18)") (class "Default")
      (node (ref "U1") (pin "AA18") (pinfunction "DRAM_D33_AA18") (pintype "bidirectional"))
    )
    (net (code "77") (name "unconnected-(U1C-DRAM_D34-PadAC18)") (class "Default")
      (node (ref "U1") (pin "AC18") (pinfunction "DRAM_D34_AC18") (pintype "bidirectional"))
    )
    (net (code "78") (name "unconnected-(U1C-DRAM_D35-PadAE19)") (class "Default")
      (node (ref "U1") (pin "AE19") (pinfunction "DRAM_D35_AE19") (pintype "bidirectional"))
    )
    (net (code "79") (name "unconnected-(U1C-DRAM_D36-PadY17)") (class "Default")
      (node (ref "U1") (pin "Y17") (pinfunction "DRAM_D36_Y17") (pintype "bidirectional"))
    )
    (net (code "80") (name "unconnected-(U1C-DRAM_D37-PadY18)") (class "Default")
      (node (ref "U1") (pin "Y18") (pinfunction "DRAM_D37_Y18") (pintype "bidirectional"))
    )
    (net (code "81") (name "unconnected-(U1C-DRAM_D38-PadAB19)") (class "Default")
      (node (ref "U1") (pin "AB19") (pinfunction "DRAM_D38_AB19") (pintype "bidirectional"))
    )
    (net (code "82") (name "unconnected-(U1C-DRAM_D39-PadAC19)") (class "Default")
      (node (ref "U1") (pin "AC19") (pinfunction "DRAM_D39_AC19") (pintype "bidirectional"))
    )
    (net (code "83") (name "unconnected-(U1C-DRAM_D40-PadY19)") (class "Default")
      (node (ref "U1") (pin "Y19") (pinfunction "DRAM_D40_Y19") (pintype "bidirectional"))
    )
    (net (code "84") (name "unconnected-(U1C-DRAM_D41-PadAB20)") (class "Default")
      (node (ref "U1") (pin "AB20") (pinfunction "DRAM_D41_AB20") (pintype "bidirectional"))
    )
    (net (code "85") (name "unconnected-(U1C-DRAM_D42-PadAB21)") (class "Default")
      (node (ref "U1") (pin "AB21") (pinfunction "DRAM_D42_AB21") (pintype "bidirectional"))
    )
    (net (code "86") (name "unconnected-(U1C-DRAM_D43-PadAD21)") (class "Default")
      (node (ref "U1") (pin "AD21") (pinfunction "DRAM_D43_AD21") (pintype "bidirectional"))
    )
    (net (code "87") (name "unconnected-(U1C-DRAM_D44-PadY20)") (class "Default")
      (node (ref "U1") (pin "Y20") (pinfunction "DRAM_D44_Y20") (pintype "bidirectional"))
    )
    (net (code "88") (name "unconnected-(U1C-DRAM_D45-PadAA20)") (class "Default")
      (node (ref "U1") (pin "AA20") (pinfunction "DRAM_D45_AA20") (pintype "bidirectional"))
    )
    (net (code "89") (name "unconnected-(U1C-DRAM_D46-PadAE21)") (class "Default")
      (node (ref "U1") (pin "AE21") (pinfunction "DRAM_D46_AE21") (pintype "bidirectional"))
    )
    (net (code "90") (name "unconnected-(U1C-DRAM_D47-PadAC21)") (class "Default")
      (node (ref "U1") (pin "AC21") (pinfunction "DRAM_D47_AC21") (pintype "bidirectional"))
    )
    (net (code "91") (name "unconnected-(U1C-DRAM_D48-PadAC22)") (class "Default")
      (node (ref "U1") (pin "AC22") (pinfunction "DRAM_D48_AC22") (pintype "bidirectional"))
    )
    (net (code "92") (name "unconnected-(U1C-DRAM_D49-PadAE22)") (class "Default")
      (node (ref "U1") (pin "AE22") (pinfunction "DRAM_D49_AE22") (pintype "bidirectional"))
    )
    (net (code "93") (name "unconnected-(U1C-DRAM_D50-PadAE24)") (class "Default")
      (node (ref "U1") (pin "AE24") (pinfunction "DRAM_D50_AE24") (pintype "bidirectional"))
    )
    (net (code "94") (name "unconnected-(U1C-DRAM_D51-PadAC24)") (class "Default")
      (node (ref "U1") (pin "AC24") (pinfunction "DRAM_D51_AC24") (pintype "bidirectional"))
    )
    (net (code "95") (name "unconnected-(U1C-DRAM_D52-PadAB22)") (class "Default")
      (node (ref "U1") (pin "AB22") (pinfunction "DRAM_D52_AB22") (pintype "bidirectional"))
    )
    (net (code "96") (name "unconnected-(U1C-DRAM_D53-PadAC23)") (class "Default")
      (node (ref "U1") (pin "AC23") (pinfunction "DRAM_D53_AC23") (pintype "bidirectional"))
    )
    (net (code "97") (name "unconnected-(U1C-DRAM_D54-PadAD25)") (class "Default")
      (node (ref "U1") (pin "AD25") (pinfunction "DRAM_D54_AD25") (pintype "bidirectional"))
    )
    (net (code "98") (name "unconnected-(U1C-DRAM_D55-PadAC25)") (class "Default")
      (node (ref "U1") (pin "AC25") (pinfunction "DRAM_D55_AC25") (pintype "bidirectional"))
    )
    (net (code "99") (name "unconnected-(U1C-DRAM_D56-PadAB25)") (class "Default")
      (node (ref "U1") (pin "AB25") (pinfunction "DRAM_D56_AB25") (pintype "bidirectional"))
    )
    (net (code "100") (name "unconnected-(U1C-DRAM_D57-PadAA21)") (class "Default")
      (node (ref "U1") (pin "AA21") (pinfunction "DRAM_D57_AA21") (pintype "bidirectional"))
    )
    (net (code "101") (name "unconnected-(U1C-DRAM_D58-PadY25)") (class "Default")
      (node (ref "U1") (pin "Y25") (pinfunction "DRAM_D58_Y25") (pintype "bidirectional"))
    )
    (net (code "102") (name "unconnected-(U1C-DRAM_D59-PadY22)") (class "Default")
      (node (ref "U1") (pin "Y22") (pinfunction "DRAM_D59_Y22") (pintype "bidirectional"))
    )
    (net (code "103") (name "unconnected-(U1C-DRAM_D60-PadAB23)") (class "Default")
      (node (ref "U1") (pin "AB23") (pinfunction "DRAM_D60_AB23") (pintype "bidirectional"))
    )
    (net (code "104") (name "unconnected-(U1C-DRAM_D61-PadAA23)") (class "Default")
      (node (ref "U1") (pin "AA23") (pinfunction "DRAM_D61_AA23") (pintype "bidirectional"))
    )
    (net (code "105") (name "unconnected-(U1C-DRAM_D62-PadY23)") (class "Default")
      (node (ref "U1") (pin "Y23") (pinfunction "DRAM_D62_Y23") (pintype "bidirectional"))
    )
    (net (code "106") (name "unconnected-(U1C-DRAM_D63-PadW25)") (class "Default")
      (node (ref "U1") (pin "W25") (pinfunction "DRAM_D63_W25") (pintype "bidirectional"))
    )
    (net (code "107") (name "unconnected-(U1C-DRAM_DQM2-PadAB8)") (class "Default")
      (node (ref "U1") (pin "AB8") (pinfunction "DRAM_DQM2_AB8") (pintype "output"))
    )
    (net (code "108") (name "unconnected-(U1C-DRAM_DQM3-PadAE10)") (class "Default")
      (node (ref "U1") (pin "AE10") (pinfunction "DRAM_DQM3_AE10") (pintype "output"))
    )
    (net (code "109") (name "unconnected-(U1C-DRAM_DQM4-PadAB18)") (class "Default")
      (node (ref "U1") (pin "AB18") (pinfunction "DRAM_DQM4_AB18") (pintype "output"))
    )
    (net (code "110") (name "unconnected-(U1C-DRAM_DQM5-PadAC20)") (class "Default")
      (node (ref "U1") (pin "AC20") (pinfunction "DRAM_DQM5_AC20") (pintype "output"))
    )
    (net (code "111") (name "unconnected-(U1C-DRAM_DQM6-PadAD24)") (class "Default")
      (node (ref "U1") (pin "AD24") (pinfunction "DRAM_DQM6_AD24") (pintype "output"))
    )
    (net (code "112") (name "unconnected-(U1C-DRAM_DQM7-PadY21)") (class "Default")
      (node (ref "U1") (pin "Y21") (pinfunction "DRAM_DQM7_Y21") (pintype "output"))
    )
    (net (code "113") (name "unconnected-(U1C-DRAM_SDCKE1-PadAA11)") (class "Default")
      (node (ref "U1") (pin "AA11") (pinfunction "DRAM_SDCKE1_AA11") (pintype "output"))
    )
    (net (code "114") (name "unconnected-(U1C-DRAM_SDCLK_1-PadAD14)") (class "Default")
      (node (ref "U1") (pin "AD14") (pinfunction "DRAM_SDCLK_1_AD14") (pintype "output"))
    )
    (net (code "115") (name "unconnected-(U1C-DRAM_SDODT1-PadAB17)") (class "Default")
      (node (ref "U1") (pin "AB17") (pinfunction "DRAM_SDODT1_AB17") (pintype "output"))
    )
    (net (code "116") (name "unconnected-(U1C-DRAM_SDQS2-PadAD8)") (class "Default")
      (node (ref "U1") (pin "AD8") (pinfunction "DRAM_SDQS2_AD8") (pintype "bidirectional"))
    )
    (net (code "117") (name "unconnected-(U1C-DRAM_SDQS3-PadAC10)") (class "Default")
      (node (ref "U1") (pin "AC10") (pinfunction "DRAM_SDQS3_AC10") (pintype "bidirectional"))
    )
    (net (code "118") (name "unconnected-(U1C-DRAM_SDQS4-PadAD18)") (class "Default")
      (node (ref "U1") (pin "AD18") (pinfunction "DRAM_SDQS4_AD18") (pintype "bidirectional"))
    )
    (net (code "119") (name "unconnected-(U1C-DRAM_SDQS5-PadAD20)") (class "Default")
      (node (ref "U1") (pin "AD20") (pinfunction "DRAM_SDQS5_AD20") (pintype "bidirectional"))
    )
    (net (code "120") (name "unconnected-(U1C-DRAM_SDQS6-PadAD23)") (class "Default")
      (node (ref "U1") (pin "AD23") (pinfunction "DRAM_SDQS6_AD23") (pintype "bidirectional"))
    )
    (net (code "121") (name "unconnected-(U1C-DRAM_SDQS7-PadAA25)") (class "Default")
      (node (ref "U1") (pin "AA25") (pinfunction "DRAM_SDQS7_AA25") (pintype "bidirectional"))
    )
    (net (code "122") (name "unconnected-(U1C-~{DRAM_SDCLK_1}-PadAE14)") (class "Default")
      (node (ref "U1") (pin "AE14") (pinfunction "~{DRAM_SDCLK_1}_AE14") (pintype "output"))
    )
    (net (code "123") (name "unconnected-(U1C-~{DRAM_SDQS2}-PadAE8)") (class "Default")
      (node (ref "U1") (pin "AE8") (pinfunction "~{DRAM_SDQS2}_AE8") (pintype "bidirectional"))
    )
    (net (code "124") (name "unconnected-(U1C-~{DRAM_SDQS3}-PadAB10)") (class "Default")
      (node (ref "U1") (pin "AB10") (pinfunction "~{DRAM_SDQS3}_AB10") (pintype "bidirectional"))
    )
    (net (code "125") (name "unconnected-(U1C-~{DRAM_SDQS4}-PadAE18)") (class "Default")
      (node (ref "U1") (pin "AE18") (pinfunction "~{DRAM_SDQS4}_AE18") (pintype "bidirectional"))
    )
    (net (code "126") (name "unconnected-(U1C-~{DRAM_SDQS5}-PadAE20)") (class "Default")
      (node (ref "U1") (pin "AE20") (pinfunction "~{DRAM_SDQS5}_AE20") (pintype "bidirectional"))
    )
    (net (code "127") (name "unconnected-(U1C-~{DRAM_SDQS6}-PadAE23)") (class "Default")
      (node (ref "U1") (pin "AE23") (pinfunction "~{DRAM_SDQS6}_AE23") (pintype "bidirectional"))
    )
    (net (code "128") (name "unconnected-(U1C-~{DRAM_SDQS7}-PadAA24)") (class "Default")
      (node (ref "U1") (pin "AA24") (pinfunction "~{DRAM_SDQS7}_AA24") (pintype "bidirectional"))
    )
  )
)
